# Bluetooth_bulb.net
KiCad netlist of a schematic drawn in Altium Designer
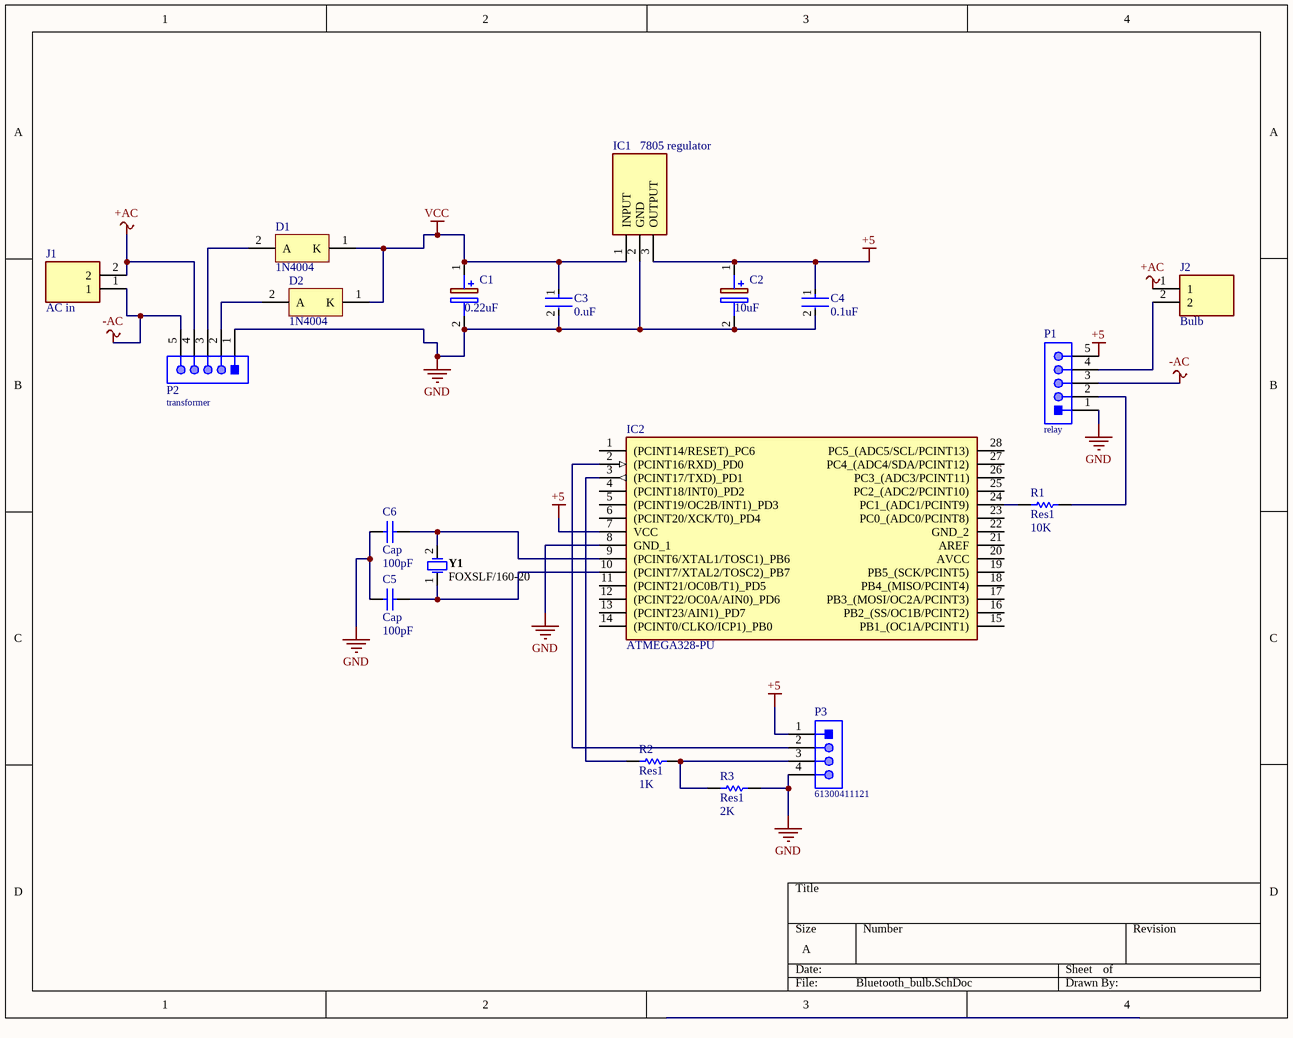
[diagram p0: Bluetooth_bulb.SchDoc]

(export (version "E")
  (design (tool "Eeschema 10.0.6"))
  (components
    (comp (ref "C1")
      (value "0.22uF")
      (footprint "SamacSys:CAPPRD200W52D500H1250")
      (description "Capacitor Polarised")
      (fields
        (field (name "MANUFACTURER_PART_NUMBER") "860010672002")
        (field (name "MOUSER PART NUMBER") "710-860010672002")
      )
      (libsource (lib "*") (part "860010672002"))
    )
    (comp (ref "C2")
      (value "10uF")
      (footprint "SamacSys:CAPPRD200W52D500H1250")
      (description "Capacitor Polarised")
      (fields
        (field (name "MANUFACTURER_PART_NUMBER") "860010672002")
        (field (name "MOUSER PART NUMBER") "710-860010672002")
      )
      (libsource (lib "*") (part "860010672002"))
    )
    (comp (ref "C3")
      (value "0.uF")
      (footprint "FP-RDE0P1-MFG")
      (description "Ceramic Capacitor 100nF ±10% 25V X7R Radial")
      (fields (field (name "TOLERANCE") "10%"))
      (libsource (lib "Altium Content Vault") (part "b4654b650e69147ec39a6b967a45e02"))
    )
    (comp (ref "C4")
      (value "0.1uF")
      (footprint "FP-RDE0P1-MFG")
      (description "Ceramic Capacitor 100nF ±10% 25V X7R Radial")
      (fields (field (name "TOLERANCE") "10%"))
      (libsource (lib "Altium Content Vault") (part "b4654b650e69147ec39a6b967a45e02"))
    )
    (comp (ref "C5")
      (value "Cap")
      (footprint "RAD-0.3")
      (description "Capacitor")
      (fields (field (name "ALTIUM_VALUE") "100pF") (field (name "PUBLISHER") "Altium Limited"))
      (libsource (lib "Miscellaneous Devices") (part "Cap"))
    )
    (comp (ref "C6")
      (value "Cap")
      (footprint "RAD-0.3")
      (description "Capacitor")
      (fields (field (name "ALTIUM_VALUE") "100pF") (field (name "PUBLISHER") "Altium Limited"))
      (libsource (lib "Miscellaneous Devices") (part "Cap"))
    )
    (comp (ref "D1")
      (value "1N4004")
      (footprint "ONSC-AXIAL_LEAD-2-59-10_P")
      (description "Standard Recovery Rectifier, 2-Pin Axial_Lead, Pb-Free, Bulk Bag")
      (fields (field (name "MANUFACTURER") "On Semiconductor"))
      (libsource (lib "Altium Content Vault") (part "ONSC-D-K1A2-2_A"))
    )
    (comp (ref "D2")
      (value "1N4004")
      (footprint "ONSC-AXIAL_LEAD-2-59-10_P")
      (description "Standard Recovery Rectifier, 2-Pin Axial_Lead, Pb-Free, Bulk Bag")
      (fields (field (name "MANUFACTURER") "On Semiconductor"))
      (libsource (lib "Altium Content Vault") (part "ONSC-D-K1A2-2_A"))
    )
    (comp (ref "IC1")
      (value "7805 regulator")
      (footprint "SamacSys:TO254P470X1028X1955-3P")
      (description "Integrated Circuit")
      (fields
        (field (name "MANUFACTURER_PART_NUMBER") "LM7805CT/NOPB")
        (field (name "MOUSER PART NUMBER") "926-LM7805CT/NOPB")
      )
      (libsource (lib "*") (part "LM7805CT_NOPB"))
    )
    (comp (ref "IC2")
      (value "ATMEGA328-PU")
      (footprint "SamacSys:DIP1016W53P254L3468H457Q28N")
      (description "Integrated Circuit")
      (fields (field (name "MOUSER PART NUMBER") "556-ATMEGA328-PU"))
      (libsource (lib "*") (part "ATMEGA328-PU"))
    )
    (comp (ref "J1")
      (value "AC in")
      (footprint "SamacSys:15462152")
      (description "Connector")
      (fields
        (field (name "MANUFACTURER_PART_NUMBER") "1546215-2")
        (field (name "MOUSER PART NUMBER") "571-1546215-2")
      )
      (libsource (lib "") (part "1546215-2_1"))
    )
    (comp (ref "J2")
      (value "Bulb")
      (footprint "SamacSys:15462152")
      (description "Connector")
      (fields
        (field (name "MANUFACTURER_PART_NUMBER") "1546215-2")
        (field (name "MOUSER PART NUMBER") "571-1546215-2")
      )
      (libsource (lib "*") (part "1546215-2"))
    )
    (comp (ref "P1")
      (value "relay")
      (footprint "61300511121")
      (description "THT Vertical Pin Header WR-PHD, Pitch 2.54 mm, Single Row, 5 pins")
      (fields
        (field (name "PART NUMBER") "61300511121")
        (field (name "MANUFACTURER") "Wurth Elektronik")
        (field (name "PUBLISHER") "WurthElektronik")
      )
      (libsource (lib "Altium Content Vault") (part "WE-CN-1P-M-R5"))
    )
    (comp (ref "P2")
      (value "transformer")
      (footprint "61300511121")
      (description "THT Vertical Pin Header WR-PHD, Pitch 2.54 mm, Single Row, 5 pins")
      (fields
        (field (name "PART NUMBER") "61300511121")
        (field (name "MANUFACTURER") "Wurth Elektronik")
        (field (name "PUBLISHER") "WurthElektronik")
      )
      (libsource (lib "") (part "WE-CN-1P-M-R5_1"))
    )
    (comp (ref "P3")
      (value "61300411121")
      (footprint "61300411121")
      (description "THT Vertical Pin Header WR-PHD, Pitch 2.54 mm, Single Row, 4 pins")
      (fields (field (name "MANUFACTURER") "Wurth Elektronik") (field (name "PUBLISHER") "WurthElektronik"))
      (libsource (lib "Altium Content Vault") (part "WE-CN-1P-M-R4"))
    )
    (comp (ref "R1")
      (value "Res1")
      (footprint "AXIAL-0.3")
      (description "Resistor")
      (fields (field (name "ALTIUM_VALUE") "10K") (field (name "PUBLISHER") "Altium Limited"))
      (libsource (lib "Miscellaneous Devices") (part "Res1"))
    )
    (comp (ref "R2")
      (value "Res1")
      (footprint "AXIAL-0.3")
      (description "Resistor")
      (fields (field (name "ALTIUM_VALUE") "1K") (field (name "PUBLISHER") "Altium Limited"))
      (libsource (lib "Miscellaneous Devices") (part "Res1"))
    )
    (comp (ref "R3")
      (value "Res1")
      (footprint "AXIAL-0.3")
      (description "Resistor")
      (fields (field (name "ALTIUM_VALUE") "2K") (field (name "PUBLISHER") "Altium Limited"))
      (libsource (lib "Miscellaneous Devices") (part "Res1"))
    )
    (comp (ref "Y1")
      (value "FOXSLF/160-20")
      (footprint "FOX-FOXSLF160-20")
      (description "Resistance Weld Thru-Hole Crystal, 16 MHz, -20 to 70 degC, 2-Pin THD, RoHS, Bulk")
      (fields (field (name "TOLERANCE") "1%"))
      (libsource (lib "Altium Content Vault") (part "XTAL-1-2-2"))
    )
  )
  (nets
    (net (code "1") (name "+5") (class "Default")
      (node (ref "C2") (pin "1") (pinfunction "+_1") (pintype "passive"))
      (node (ref "C4") (pin "1") (pinfunction "1_1") (pintype "passive"))
      (node (ref "IC1") (pin "3") (pinfunction "OUTPUT_3") (pintype "passive"))
      (node (ref "IC2") (pin "7") (pinfunction "VCC_7") (pintype "power_in"))
      (node (ref "P1") (pin "5") (pinfunction "5_5") (pintype "passive"))
      (node (ref "P3") (pin "1") (pinfunction "1_1") (pintype "passive"))
    )
    (net (code "2") (name "+AC") (class "Default")
      (node (ref "J1") (pin "2") (pinfunction "2_2") (pintype "passive"))
      (node (ref "J2") (pin "1") (pinfunction "1_1") (pintype "passive"))
      (node (ref "P2") (pin "4") (pinfunction "4_4") (pintype "passive"))
    )
    (net (code "3") (name "-AC") (class "Default")
      (node (ref "J1") (pin "1") (pinfunction "1_1") (pintype "passive"))
      (node (ref "P1") (pin "3") (pinfunction "3_3") (pintype "passive"))
      (node (ref "P2") (pin "5") (pinfunction "5_5") (pintype "passive"))
    )
    (net (code "4") (name "GND") (class "Default")
      (node (ref "C1") (pin "2") (pinfunction "-_2") (pintype "passive"))
      (node (ref "C2") (pin "2") (pinfunction "-_2") (pintype "passive"))
      (node (ref "C3") (pin "2") (pinfunction "2_2") (pintype "passive"))
      (node (ref "C4") (pin "2") (pinfunction "2_2") (pintype "passive"))
      (node (ref "C5") (pin "2") (pinfunction "2_2") (pintype "passive"))
      (node (ref "C6") (pin "2") (pinfunction "2_2") (pintype "passive"))
      (node (ref "IC1") (pin "2") (pinfunction "GND_2") (pintype "passive"))
      (node (ref "IC2") (pin "8") (pinfunction "GND_1_8") (pintype "power_in"))
      (node (ref "P1") (pin "1") (pinfunction "1_1") (pintype "passive"))
      (node (ref "P2") (pin "1") (pinfunction "1_1") (pintype "passive"))
      (node (ref "P3") (pin "4") (pinfunction "4_4") (pintype "passive"))
      (node (ref "R3") (pin "1") (pinfunction "1_1") (pintype "passive"))
    )
    (net (code "5") (name "Net-(D1-A)") (class "Default")
      (node (ref "D1") (pin "2") (pinfunction "A_2") (pintype "passive"))
      (node (ref "P2") (pin "3") (pinfunction "3_3") (pintype "passive"))
    )
    (net (code "6") (name "Net-(D2-A)") (class "Default")
      (node (ref "D2") (pin "2") (pinfunction "A_2") (pintype "passive"))
      (node (ref "P2") (pin "2") (pinfunction "2_2") (pintype "passive"))
    )
    (net (code "7") (name "Net-(IC2-(PCINT6{slash}XTAL1{slash}TOSC1)_PB6)") (class "Default")
      (node (ref "C6") (pin "1") (pinfunction "1_1") (pintype "passive"))
      (node (ref "IC2") (pin "9") (pinfunction "(PCINT6/XTAL1/TOSC1)_PB6_9") (pintype "passive"))
      (node (ref "Y1") (pin "2") (pinfunction "2_2") (pintype "passive"))
    )
    (net (code "8") (name "Net-(IC2-(PCINT7{slash}XTAL2{slash}TOSC2)_PB7)") (class "Default")
      (node (ref "C5") (pin "1") (pinfunction "1_1") (pintype "passive"))
      (node (ref "IC2") (pin "10") (pinfunction "(PCINT7/XTAL2/TOSC2)_PB7_10") (pintype "passive"))
      (node (ref "Y1") (pin "1") (pinfunction "1_1") (pintype "passive"))
    )
    (net (code "9") (name "Net-(IC2-(PCINT16{slash}RXD)_PD0)") (class "Default")
      (node (ref "IC2") (pin "2") (pinfunction "(PCINT16/RXD)_PD0_2") (pintype "input"))
      (node (ref "P3") (pin "2") (pinfunction "2_2") (pintype "passive"))
    )
    (net (code "10") (name "Net-(IC2-(PCINT17{slash}TXD)_PD1)") (class "Default")
      (node (ref "IC2") (pin "3") (pinfunction "(PCINT17/TXD)_PD1_3") (pintype "output"))
      (node (ref "R2") (pin "1") (pinfunction "1_1") (pintype "passive"))
    )
    (net (code "11") (name "Net-(IC2-PC1_(ADC1{slash}PCINT9))") (class "Default")
      (node (ref "IC2") (pin "24") (pinfunction "PC1_(ADC1/PCINT9)_24") (pintype "passive"))
      (node (ref "R1") (pin "1") (pinfunction "1_1") (pintype "passive"))
    )
    (net (code "12") (name "Net-(J2-Pad2)") (class "Default")
      (node (ref "J2") (pin "2") (pinfunction "2_2") (pintype "passive"))
      (node (ref "P1") (pin "4") (pinfunction "4_4") (pintype "passive"))
    )
    (net (code "13") (name "Net-(P1-Pad2)") (class "Default")
      (node (ref "P1") (pin "2") (pinfunction "2_2") (pintype "passive"))
      (node (ref "R1") (pin "2") (pinfunction "2_2") (pintype "passive"))
    )
    (net (code "14") (name "Net-(P3-Pad3)") (class "Default")
      (node (ref "P3") (pin "3") (pinfunction "3_3") (pintype "passive"))
      (node (ref "R2") (pin "2") (pinfunction "2_2") (pintype "passive"))
      (node (ref "R3") (pin "2") (pinfunction "2_2") (pintype "passive"))
    )
    (net (code "15") (name "VCC") (class "Default")
      (node (ref "C1") (pin "1") (pinfunction "+_1") (pintype "passive"))
      (node (ref "C3") (pin "1") (pinfunction "1_1") (pintype "passive"))
      (node (ref "D1") (pin "1") (pinfunction "K_1") (pintype "passive"))
      (node (ref "D2") (pin "1") (pinfunction "K_1") (pintype "passive"))
      (node (ref "IC1") (pin "1") (pinfunction "INPUT_1") (pintype "passive"))
    )
    (net (code "16") (name "unconnected-(IC2-(PCINT0{slash}CLKO{slash}ICP1)_PB0-Pad14)") (class "Default")
      (node (ref "IC2") (pin "14") (pinfunction "(PCINT0/CLKO/ICP1)_PB0_14") (pintype "passive"))
    )
    (net (code "17") (name "unconnected-(IC2-(PCINT14{slash}RESET)_PC6-Pad1)") (class "Default")
      (node (ref "IC2") (pin "1") (pinfunction "(PCINT14/RESET)_PC6_1") (pintype "passive"))
    )
    (net (code "18") (name "unconnected-(IC2-(PCINT18{slash}INT0)_PD2-Pad4)") (class "Default")
      (node (ref "IC2") (pin "4") (pinfunction "(PCINT18/INT0)_PD2_4") (pintype "passive"))
    )
    (net (code "19") (name "unconnected-(IC2-(PCINT19{slash}OC2B{slash}INT1)_PD3-Pad5)") (class "Default")
      (node (ref "IC2") (pin "5") (pinfunction "(PCINT19/OC2B/INT1)_PD3_5") (pintype "passive"))
    )
    (net (code "20") (name "unconnected-(IC2-(PCINT20{slash}XCK{slash}T0)_PD4-Pad6)") (class "Default")
      (node (ref "IC2") (pin "6") (pinfunction "(PCINT20/XCK/T0)_PD4_6") (pintype "passive"))
    )
    (net (code "21") (name "unconnected-(IC2-(PCINT21{slash}OC0B{slash}T1)_PD5-Pad11)") (class "Default")
      (node (ref "IC2") (pin "11") (pinfunction "(PCINT21/OC0B/T1)_PD5_11") (pintype "passive"))
    )
    (net (code "22") (name "unconnected-(IC2-(PCINT22{slash}OC0A{slash}AIN0)_PD6-Pad12)") (class "Default")
      (node (ref "IC2") (pin "12") (pinfunction "(PCINT22/OC0A/AIN0)_PD6_12") (pintype "passive"))
    )
    (net (code "23") (name "unconnected-(IC2-(PCINT23{slash}AIN1)_PD7-Pad13)") (class "Default")
      (node (ref "IC2") (pin "13") (pinfunction "(PCINT23/AIN1)_PD7_13") (pintype "passive"))
    )
    (net (code "24") (name "unconnected-(IC2-AREF-Pad21)") (class "Default")
      (node (ref "IC2") (pin "21") (pinfunction "AREF_21") (pintype "passive"))
    )
    (net (code "25") (name "unconnected-(IC2-AVCC-Pad20)") (class "Default")
      (node (ref "IC2") (pin "20") (pinfunction "AVCC_20") (pintype "power_in"))
    )
    (net (code "26") (name "unconnected-(IC2-GND_2-Pad22)") (class "Default")
      (node (ref "IC2") (pin "22") (pinfunction "GND_2_22") (pintype "power_in"))
    )
    (net (code "27") (name "unconnected-(IC2-PB1_(OC1A{slash}PCINT1)-Pad15)") (class "Default")
      (node (ref "IC2") (pin "15") (pinfunction "PB1_(OC1A/PCINT1)_15") (pintype "passive"))
    )
    (net (code "28") (name "unconnected-(IC2-PB2_(SS{slash}OC1B{slash}PCINT2)-Pad16)") (class "Default")
      (node (ref "IC2") (pin "16") (pinfunction "PB2_(SS/OC1B/PCINT2)_16") (pintype "passive"))
    )
    (net (code "29") (name "unconnected-(IC2-PB3_(MOSI{slash}OC2A{slash}PCINT3)-Pad17)") (class "Default")
      (node (ref "IC2") (pin "17") (pinfunction "PB3_(MOSI/OC2A/PCINT3)_17") (pintype "passive"))
    )
    (net (code "30") (name "unconnected-(IC2-PB4_(MISO{slash}PCINT4)-Pad18)") (class "Default")
      (node (ref "IC2") (pin "18") (pinfunction "PB4_(MISO/PCINT4)_18") (pintype "passive"))
    )
    (net (code "31") (name "unconnected-(IC2-PB5_(SCK{slash}PCINT5)-Pad19)") (class "Default")
      (node (ref "IC2") (pin "19") (pinfunction "PB5_(SCK/PCINT5)_19") (pintype "passive"))
    )
    (net (code "32") (name "unconnected-(IC2-PC0_(ADC0{slash}PCINT8)-Pad23)") (class "Default")
      (node (ref "IC2") (pin "23") (pinfunction "PC0_(ADC0/PCINT8)_23") (pintype "passive"))
    )
    (net (code "33") (name "unconnected-(IC2-PC2_(ADC2{slash}PCINT10)-Pad25)") (class "Default")
      (node (ref "IC2") (pin "25") (pinfunction "PC2_(ADC2/PCINT10)_25") (pintype "passive"))
    )
    (net (code "34") (name "unconnected-(IC2-PC3_(ADC3{slash}PCINT11)-Pad26)") (class "Default")
      (node (ref "IC2") (pin "26") (pinfunction "PC3_(ADC3/PCINT11)_26") (pintype "passive"))
    )
    (net (code "35") (name "unconnected-(IC2-PC4_(ADC4{slash}SDA{slash}PCINT12)-Pad27)") (class "Default")
      (node (ref "IC2") (pin "27") (pinfunction "PC4_(ADC4/SDA/PCINT12)_27") (pintype "passive"))
    )
    (net (code "36") (name "unconnected-(IC2-PC5_(ADC5{slash}SCL{slash}PCINT13)-Pad28)") (class "Default")
      (node (ref "IC2") (pin "28") (pinfunction "PC5_(ADC5/SCL/PCINT13)_28") (pintype "passive"))
    )
  )
)
